# NNLightSwitcher_DDR3.net
KiCad netlist of a schematic drawn in Altium Designer
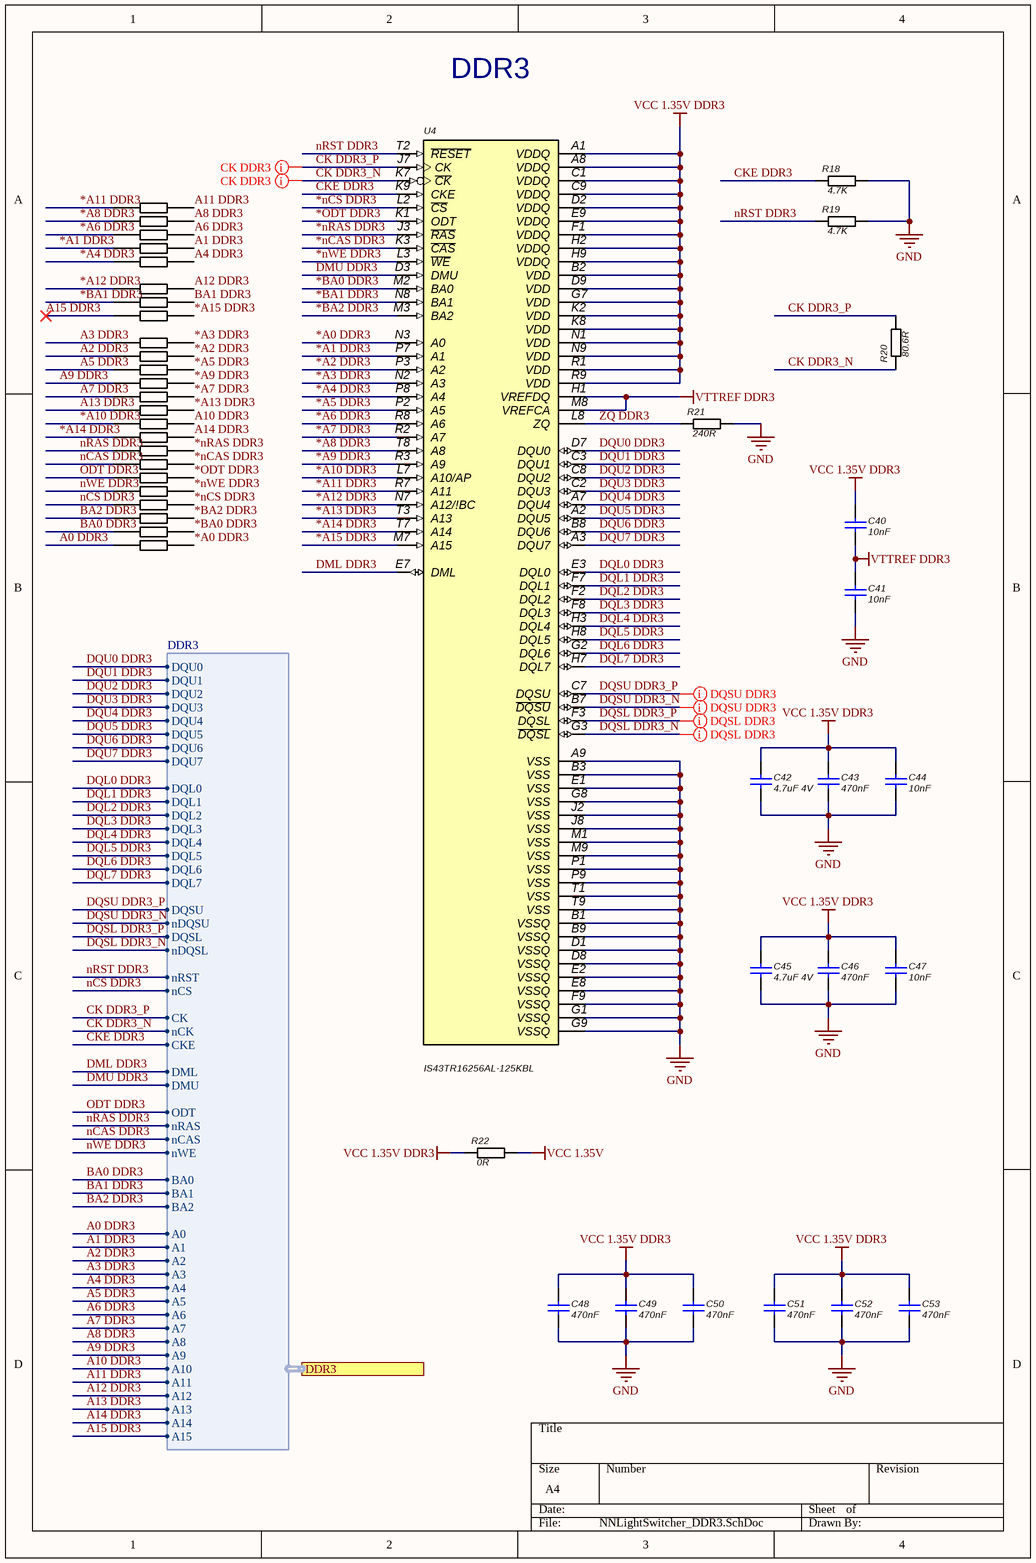
[diagram p0: NNLightSwitcher_DDR3.SchDoc]

(export (version "E")
  (design (tool "Eeschema 10.0.6"))
  (components
    (comp (ref "C40")
      (value "10nF")
      (footprint "0402")
      (libsource (lib "NNLightSwitcher") (part "Capacitor 10nF"))
    )
    (comp (ref "C41")
      (value "10nF")
      (footprint "0402")
      (libsource (lib "NNLightSwitcher") (part "Capacitor 10nF"))
    )
    (comp (ref "C42")
      (value "4.7uF 4V")
      (footprint "0402")
      (libsource (lib "NNLightSwitcher") (part "Capacitor 4.7uF 4V"))
    )
    (comp (ref "C43")
      (value "470nF")
      (footprint "0402")
      (libsource (lib "NNLightSwitcher") (part "Capacitor 470nF"))
    )
    (comp (ref "C44")
      (value "10nF")
      (footprint "0402")
      (libsource (lib "NNLightSwitcher") (part "Capacitor 10nF"))
    )
    (comp (ref "C45")
      (value "4.7uF 4V")
      (footprint "0402")
      (libsource (lib "NNLightSwitcher") (part "Capacitor 4.7uF 4V"))
    )
    (comp (ref "C46")
      (value "470nF")
      (footprint "0402")
      (libsource (lib "NNLightSwitcher") (part "Capacitor 470nF"))
    )
    (comp (ref "C47")
      (value "10nF")
      (footprint "0402")
      (libsource (lib "NNLightSwitcher") (part "Capacitor 10nF"))
    )
    (comp (ref "C48")
      (value "470nF")
      (footprint "0402")
      (libsource (lib "NNLightSwitcher") (part "Capacitor 470nF"))
    )
    (comp (ref "C49")
      (value "470nF")
      (footprint "0402")
      (libsource (lib "NNLightSwitcher") (part "Capacitor 470nF"))
    )
    (comp (ref "C50")
      (value "470nF")
      (footprint "0402")
      (libsource (lib "NNLightSwitcher") (part "Capacitor 470nF"))
    )
    (comp (ref "C51")
      (value "470nF")
      (footprint "0402")
      (libsource (lib "NNLightSwitcher") (part "Capacitor 470nF"))
    )
    (comp (ref "C52")
      (value "470nF")
      (footprint "0402")
      (libsource (lib "NNLightSwitcher") (part "Capacitor 470nF"))
    )
    (comp (ref "C53")
      (value "470nF")
      (footprint "0402")
      (libsource (lib "NNLightSwitcher") (part "Capacitor 470nF"))
    )
    (comp (ref "R18")
      (value "4.7K")
      (footprint "0402")
      (libsource (lib "NNLightSwitcher") (part "Resistor 4.7K"))
    )
    (comp (ref "R19")
      (value "4.7K")
      (footprint "0402")
      (libsource (lib "NNLightSwitcher") (part "Resistor 4.7K"))
    )
    (comp (ref "R20")
      (value "80.6R")
      (footprint "0402")
      (libsource (lib "NNLightSwitcher") (part "Resistor 80.6R"))
    )
    (comp (ref "R21")
      (value "240R")
      (footprint "0402")
      (libsource (lib "NNLightSwitcher") (part "Resistor 240R"))
    )
    (comp (ref "R22")
      (value "0R")
      (footprint "0402")
      (libsource (lib "NNLightSwitcher") (part "Resistor 0R"))
    )
    (comp (ref "RN1")
      (value "EXB-2HV431JV")
      (footprint "*RESCAXE50P380X160X55-16N")
      (description "Res Thick Film Array")
      (libsource (lib "NNLightSwitcher") (part "EXB-2HV431JV"))
    )
    (comp (ref "RN2")
      (value "EXB-2HV431JV")
      (footprint "*RESCAXE50P380X160X55-16N")
      (description "Res Thick Film Array")
      (libsource (lib "NNLightSwitcher") (part "EXB-2HV431JV"))
    )
    (comp (ref "RN3")
      (value "EXB-2HV431JV")
      (footprint "*RESCAXE50P380X160X55-16N")
      (description "Res Thick Film Array")
      (libsource (lib "NNLightSwitcher") (part "EXB-2HV431JV"))
    )
    (comp (ref "U4")
      (value "IS43TR16256AL-125KBL")
      (footprint "*BGA96C80P9X16_900X1300X120_IS43TR16256AL-125KBL(Primary)")
      (description "4G, 1.35V, DDR3L, 256Mx16, 1600MT/s @ 11-11-11, 96 ball BGA _9mm x13mm_ RoHS")
      (libsource (lib "NNLightSwitcher") (part "IS43TR16256AL-125KBL"))
    )
  )
  (nets
    (net (code "2") (name "/*A0 DDR3") (class "Default")
      (node (ref "RN3") (pin "9") (pinfunction "2_9") (pintype "passive"))
      (node (ref "U4") (pin "N3") (pinfunction "A0_N3") (pintype "input"))
    )
    (net (code "3") (name "/*A1 DDR3") (class "Default")
      (node (ref "RN1") (pin "4") (pinfunction "1_4") (pintype "passive"))
      (node (ref "U4") (pin "P7") (pinfunction "A1_P7") (pintype "input"))
    )
    (net (code "4") (name "/*A2 DDR3") (class "Default")
      (node (ref "RN2") (pin "15") (pinfunction "2_15") (pintype "passive"))
      (node (ref "U4") (pin "P3") (pinfunction "A2_P3") (pintype "input"))
    )
    (net (code "5") (name "/*A3 DDR3") (class "Default")
      (node (ref "RN2") (pin "16") (pinfunction "2_16") (pintype "passive"))
      (node (ref "U4") (pin "N2") (pinfunction "A3_N2") (pintype "input"))
    )
    (net (code "6") (name "/*A4 DDR3") (class "Default")
      (node (ref "RN1") (pin "5") (pinfunction "1_5") (pintype "passive"))
      (node (ref "U4") (pin "P8") (pinfunction "A4_P8") (pintype "input"))
    )
    (net (code "7") (name "/*A5 DDR3") (class "Default")
      (node (ref "RN2") (pin "14") (pinfunction "2_14") (pintype "passive"))
      (node (ref "U4") (pin "P2") (pinfunction "A5_P2") (pintype "input"))
    )
    (net (code "8") (name "/*A6 DDR3") (class "Default")
      (node (ref "RN1") (pin "3") (pinfunction "1_3") (pintype "passive"))
      (node (ref "U4") (pin "R8") (pinfunction "A6_R8") (pintype "input"))
    )
    (net (code "9") (name "/*A7 DDR3") (class "Default")
      (node (ref "RN2") (pin "12") (pinfunction "2_12") (pintype "passive"))
      (node (ref "U4") (pin "R2") (pinfunction "A7_R2") (pintype "input"))
    )
    (net (code "10") (name "/*A8 DDR3") (class "Default")
      (node (ref "RN1") (pin "2") (pinfunction "1_2") (pintype "passive"))
      (node (ref "U4") (pin "T8") (pinfunction "A8_T8") (pintype "input"))
    )
    (net (code "11") (name "/*A9 DDR3") (class "Default")
      (node (ref "RN2") (pin "13") (pinfunction "2_13") (pintype "passive"))
      (node (ref "U4") (pin "R3") (pinfunction "A9_R3") (pintype "input"))
    )
    (net (code "12") (name "/*A10 DDR3") (class "Default")
      (node (ref "RN2") (pin "7") (pinfunction "1_7") (pintype "passive"))
      (node (ref "U4") (pin "L7") (pinfunction "A10/AP_L7") (pintype "input"))
    )
    (net (code "13") (name "/*A11 DDR3") (class "Default")
      (node (ref "RN1") (pin "1") (pinfunction "1_1") (pintype "passive"))
      (node (ref "U4") (pin "R7") (pinfunction "A11_R7") (pintype "input"))
    )
    (net (code "14") (name "/*A12 DDR3") (class "Default")
      (node (ref "RN1") (pin "6") (pinfunction "1_6") (pintype "passive"))
      (node (ref "U4") (pin "N7") (pinfunction "A12/!BC_N7") (pintype "input"))
    )
    (net (code "15") (name "/*A13 DDR3") (class "Default")
      (node (ref "RN2") (pin "11") (pinfunction "2_11") (pintype "passive"))
      (node (ref "U4") (pin "T3") (pinfunction "A13_T3") (pintype "input"))
    )
    (net (code "16") (name "/*A14 DDR3") (class "Default")
      (node (ref "RN2") (pin "8") (pinfunction "1_8") (pintype "passive"))
      (node (ref "U4") (pin "T7") (pinfunction "A14_T7") (pintype "input"))
    )
    (net (code "17") (name "/*A15 DDR3") (class "Default")
      (node (ref "RN1") (pin "8") (pinfunction "1_8") (pintype "passive"))
      (node (ref "U4") (pin "M7") (pinfunction "A15_M7") (pintype "input"))
    )
    (net (code "18") (name "/*BA0 DDR3") (class "Default")
      (node (ref "RN3") (pin "10") (pinfunction "2_10") (pintype "passive"))
      (node (ref "U4") (pin "M2") (pinfunction "BA0_M2") (pintype "input"))
    )
    (net (code "19") (name "/*BA1 DDR3") (class "Default")
      (node (ref "RN1") (pin "7") (pinfunction "1_7") (pintype "passive"))
      (node (ref "U4") (pin "N8") (pinfunction "BA1_N8") (pintype "input"))
    )
    (net (code "20") (name "/*BA2 DDR3") (class "Default")
      (node (ref "RN3") (pin "11") (pinfunction "2_11") (pintype "passive"))
      (node (ref "U4") (pin "M3") (pinfunction "BA2_M3") (pintype "input"))
    )
    (net (code "21") (name "/*ODT DDR3") (class "Default")
      (node (ref "RN3") (pin "14") (pinfunction "2_14") (pintype "passive"))
      (node (ref "U4") (pin "K1") (pinfunction "ODT_K1") (pintype "input"))
    )
    (net (code "22") (name "/*nCAS DDR3") (class "Default")
      (node (ref "RN3") (pin "15") (pinfunction "2_15") (pintype "passive"))
      (node (ref "U4") (pin "K3") (pinfunction "~{CAS}_K3") (pintype "input"))
    )
    (net (code "23") (name "/*nCS DDR3") (class "Default")
      (node (ref "RN3") (pin "12") (pinfunction "2_12") (pintype "passive"))
      (node (ref "U4") (pin "L2") (pinfunction "~{CS}_L2") (pintype "input"))
    )
    (net (code "24") (name "/*nRAS DDR3") (class "Default")
      (node (ref "RN3") (pin "16") (pinfunction "2_16") (pintype "passive"))
      (node (ref "U4") (pin "J3") (pinfunction "~{RAS}_J3") (pintype "input"))
    )
    (net (code "25") (name "/*nWE DDR3") (class "Default")
      (node (ref "RN3") (pin "13") (pinfunction "2_13") (pintype "passive"))
      (node (ref "U4") (pin "L3") (pinfunction "~{WE}_L3") (pintype "input"))
    )
    (net (code "26") (name "/A0 DDR3") (class "Default")
      (node (ref "RN3") (pin "8") (pinfunction "1_8") (pintype "passive"))
    )
    (net (code "27") (name "/A1 DDR3") (class "Default")
      (node (ref "RN1") (pin "13") (pinfunction "2_13") (pintype "passive"))
    )
    (net (code "28") (name "/A2 DDR3") (class "Default")
      (node (ref "RN2") (pin "2") (pinfunction "1_2") (pintype "passive"))
    )
    (net (code "29") (name "/A3 DDR3") (class "Default")
      (node (ref "RN2") (pin "1") (pinfunction "1_1") (pintype "passive"))
    )
    (net (code "30") (name "/A4 DDR3") (class "Default")
      (node (ref "RN1") (pin "12") (pinfunction "2_12") (pintype "passive"))
    )
    (net (code "31") (name "/A5 DDR3") (class "Default")
      (node (ref "RN2") (pin "3") (pinfunction "1_3") (pintype "passive"))
    )
    (net (code "32") (name "/A6 DDR3") (class "Default")
      (node (ref "RN1") (pin "14") (pinfunction "2_14") (pintype "passive"))
    )
    (net (code "33") (name "/A7 DDR3") (class "Default")
      (node (ref "RN2") (pin "5") (pinfunction "1_5") (pintype "passive"))
    )
    (net (code "34") (name "/A8 DDR3") (class "Default")
      (node (ref "RN1") (pin "15") (pinfunction "2_15") (pintype "passive"))
    )
    (net (code "35") (name "/A9 DDR3") (class "Default")
      (node (ref "RN2") (pin "4") (pinfunction "1_4") (pintype "passive"))
    )
    (net (code "36") (name "/A10 DDR3") (class "Default")
      (node (ref "RN2") (pin "10") (pinfunction "2_10") (pintype "passive"))
    )
    (net (code "37") (name "/A11 DDR3") (class "Default")
      (node (ref "RN1") (pin "16") (pinfunction "2_16") (pintype "passive"))
    )
    (net (code "38") (name "/A12 DDR3") (class "Default")
      (node (ref "RN1") (pin "11") (pinfunction "2_11") (pintype "passive"))
    )
    (net (code "39") (name "/A13 DDR3") (class "Default")
      (node (ref "RN2") (pin "6") (pinfunction "1_6") (pintype "passive"))
    )
    (net (code "40") (name "/A14 DDR3") (class "Default")
      (node (ref "RN2") (pin "9") (pinfunction "2_9") (pintype "passive"))
    )
    (net (code "41") (name "/A15 DDR3") (class "Default")
      (node (ref "RN1") (pin "9") (pinfunction "2_9") (pintype "passive"))
    )
    (net (code "42") (name "/BA0 DDR3") (class "Default")
      (node (ref "RN3") (pin "7") (pinfunction "1_7") (pintype "passive"))
    )
    (net (code "43") (name "/BA1 DDR3") (class "Default")
      (node (ref "RN1") (pin "10") (pinfunction "2_10") (pintype "passive"))
    )
    (net (code "44") (name "/BA2 DDR3") (class "Default")
      (node (ref "RN3") (pin "6") (pinfunction "1_6") (pintype "passive"))
    )
    (net (code "45") (name "/CK DDR3_N") (class "Default")
      (node (ref "R20") (pin "1") (pinfunction "1_1") (pintype "passive"))
      (node (ref "U4") (pin "K7") (pinfunction "~{CK}_K7") (pintype "input"))
    )
    (net (code "46") (name "/CK DDR3_P") (class "Default")
      (node (ref "R20") (pin "2") (pinfunction "2_2") (pintype "passive"))
      (node (ref "U4") (pin "J7") (pinfunction "CK_J7") (pintype "input"))
    )
    (net (code "47") (name "/CKE DDR3") (class "Default")
      (node (ref "R18") (pin "1") (pinfunction "1_1") (pintype "passive"))
      (node (ref "U4") (pin "K9") (pinfunction "CKE_K9") (pintype "input"))
    )
    (net (code "48") (name "/DML DDR3") (class "Default")
      (node (ref "U4") (pin "E7") (pinfunction "DML_E7") (pintype "bidirectional"))
    )
    (net (code "49") (name "/DMU DDR3") (class "Default")
      (node (ref "U4") (pin "D3") (pinfunction "DMU_D3") (pintype "input"))
    )
    (net (code "50") (name "/DQL0 DDR3") (class "Default")
      (node (ref "U4") (pin "E3") (pinfunction "DQL0_E3") (pintype "bidirectional"))
    )
    (net (code "51") (name "/DQL1 DDR3") (class "Default")
      (node (ref "U4") (pin "F7") (pinfunction "DQL1_F7") (pintype "bidirectional"))
    )
    (net (code "52") (name "/DQL2 DDR3") (class "Default")
      (node (ref "U4") (pin "F2") (pinfunction "DQL2_F2") (pintype "bidirectional"))
    )
    (net (code "53") (name "/DQL3 DDR3") (class "Default")
      (node (ref "U4") (pin "F8") (pinfunction "DQL3_F8") (pintype "bidirectional"))
    )
    (net (code "54") (name "/DQL4 DDR3") (class "Default")
      (node (ref "U4") (pin "H3") (pinfunction "DQL4_H3") (pintype "bidirectional"))
    )
    (net (code "55") (name "/DQL5 DDR3") (class "Default")
      (node (ref "U4") (pin "H8") (pinfunction "DQL5_H8") (pintype "bidirectional"))
    )
    (net (code "56") (name "/DQL6 DDR3") (class "Default")
      (node (ref "U4") (pin "G2") (pinfunction "DQL6_G2") (pintype "bidirectional"))
    )
    (net (code "57") (name "/DQL7 DDR3") (class "Default")
      (node (ref "U4") (pin "H7") (pinfunction "DQL7_H7") (pintype "bidirectional"))
    )
    (net (code "58") (name "/DQSL DDR3_N") (class "Default")
      (node (ref "U4") (pin "G3") (pinfunction "~{DQSL}_G3") (pintype "bidirectional"))
    )
    (net (code "59") (name "/DQSL DDR3_P") (class "Default")
      (node (ref "U4") (pin "F3") (pinfunction "DQSL_F3") (pintype "bidirectional"))
    )
    (net (code "60") (name "/DQSU DDR3_N") (class "Default")
      (node (ref "U4") (pin "B7") (pinfunction "~{DQSU}_B7") (pintype "bidirectional"))
    )
    (net (code "61") (name "/DQSU DDR3_P") (class "Default")
      (node (ref "U4") (pin "C7") (pinfunction "DQSU_C7") (pintype "bidirectional"))
    )
    (net (code "62") (name "/DQU0 DDR3") (class "Default")
      (node (ref "U4") (pin "D7") (pinfunction "DQU0_D7") (pintype "bidirectional"))
    )
    (net (code "63") (name "/DQU1 DDR3") (class "Default")
      (node (ref "U4") (pin "C3") (pinfunction "DQU1_C3") (pintype "bidirectional"))
    )
    (net (code "64") (name "/DQU2 DDR3") (class "Default")
      (node (ref "U4") (pin "C8") (pinfunction "DQU2_C8") (pintype "bidirectional"))
    )
    (net (code "65") (name "/DQU3 DDR3") (class "Default")
      (node (ref "U4") (pin "C2") (pinfunction "DQU3_C2") (pintype "bidirectional"))
    )
    (net (code "66") (name "/DQU4 DDR3") (class "Default")
      (node (ref "U4") (pin "A7") (pinfunction "DQU4_A7") (pintype "bidirectional"))
    )
    (net (code "67") (name "/DQU5 DDR3") (class "Default")
      (node (ref "U4") (pin "A2") (pinfunction "DQU5_A2") (pintype "bidirectional"))
    )
    (net (code "68") (name "/DQU6 DDR3") (class "Default")
      (node (ref "U4") (pin "B8") (pinfunction "DQU6_B8") (pintype "bidirectional"))
    )
    (net (code "69") (name "/DQU7 DDR3") (class "Default")
      (node (ref "U4") (pin "A3") (pinfunction "DQU7_A3") (pintype "bidirectional"))
    )
    (net (code "70") (name "/ODT DDR3") (class "Default")
      (node (ref "RN3") (pin "3") (pinfunction "1_3") (pintype "passive"))
    )
    (net (code "71") (name "/ZQ DDR3") (class "Default")
      (node (ref "R21") (pin "1") (pinfunction "1_1") (pintype "passive"))
      (node (ref "U4") (pin "L8") (pinfunction "ZQ_L8") (pintype "power_in"))
    )
    (net (code "72") (name "/nCAS DDR3") (class "Default")
      (node (ref "RN3") (pin "2") (pinfunction "1_2") (pintype "passive"))
    )
    (net (code "73") (name "/nCS DDR3") (class "Default")
      (node (ref "RN3") (pin "5") (pinfunction "1_5") (pintype "passive"))
    )
    (net (code "74") (name "/nRAS DDR3") (class "Default")
      (node (ref "RN3") (pin "1") (pinfunction "1_1") (pintype "passive"))
    )
    (net (code "75") (name "/nRST DDR3") (class "Default")
      (node (ref "R19") (pin "1") (pinfunction "1_1") (pintype "passive"))
      (node (ref "U4") (pin "T2") (pinfunction "~{RESET}_T2") (pintype "input"))
    )
    (net (code "76") (name "/nWE DDR3") (class "Default")
      (node (ref "RN3") (pin "4") (pinfunction "1_4") (pintype "passive"))
    )
    (net (code "78") (name "GND") (class "Default")
      (node (ref "C41") (pin "2") (pinfunction "2_2") (pintype "passive"))
      (node (ref "C42") (pin "2") (pinfunction "2_2") (pintype "passive"))
      (node (ref "C43") (pin "2") (pinfunction "2_2") (pintype "passive"))
      (node (ref "C44") (pin "2") (pinfunction "2_2") (pintype "passive"))
      (node (ref "C45") (pin "2") (pinfunction "2_2") (pintype "passive"))
      (node (ref "C46") (pin "2") (pinfunction "2_2") (pintype "passive"))
      (node (ref "C47") (pin "2") (pinfunction "2_2") (pintype "passive"))
      (node (ref "C48") (pin "2") (pinfunction "2_2") (pintype "passive"))
      (node (ref "C49") (pin "2") (pinfunction "2_2") (pintype "passive"))
      (node (ref "C50") (pin "2") (pinfunction "2_2") (pintype "passive"))
      (node (ref "C51") (pin "2") (pinfunction "2_2") (pintype "passive"))
      (node (ref "C52") (pin "2") (pinfunction "2_2") (pintype "passive"))
      (node (ref "C53") (pin "2") (pinfunction "2_2") (pintype "passive"))
      (node (ref "R18") (pin "2") (pinfunction "2_2") (pintype "passive"))
      (node (ref "R19") (pin "2") (pinfunction "2_2") (pintype "passive"))
      (node (ref "R21") (pin "2") (pinfunction "2_2") (pintype "passive"))
      (node (ref "U4") (pin "A9") (pinfunction "VSS_A9") (pintype "power_in"))
      (node (ref "U4") (pin "B1") (pinfunction "VSSQ_B1") (pintype "power_in"))
      (node (ref "U4") (pin "B3") (pinfunction "VSS_B3") (pintype "power_in"))
      (node (ref "U4") (pin "B9") (pinfunction "VSSQ_B9") (pintype "power_in"))
      (node (ref "U4") (pin "D1") (pinfunction "VSSQ_D1") (pintype "power_in"))
      (node (ref "U4") (pin "D8") (pinfunction "VSSQ_D8") (pintype "power_in"))
      (node (ref "U4") (pin "E1") (pinfunction "VSS_E1") (pintype "power_in"))
      (node (ref "U4") (pin "E2") (pinfunction "VSSQ_E2") (pintype "power_in"))
      (node (ref "U4") (pin "E8") (pinfunction "VSSQ_E8") (pintype "power_in"))
      (node (ref "U4") (pin "F9") (pinfunction "VSSQ_F9") (pintype "power_in"))
      (node (ref "U4") (pin "G1") (pinfunction "VSSQ_G1") (pintype "power_in"))
      (node (ref "U4") (pin "G8") (pinfunction "VSS_G8") (pintype "power_in"))
      (node (ref "U4") (pin "G9") (pinfunction "VSSQ_G9") (pintype "power_in"))
      (node (ref "U4") (pin "J2") (pinfunction "VSS_J2") (pintype "power_in"))
      (node (ref "U4") (pin "J8") (pinfunction "VSS_J8") (pintype "power_in"))
      (node (ref "U4") (pin "M1") (pinfunction "VSS_M1") (pintype "power_in"))
      (node (ref "U4") (pin "M9") (pinfunction "VSS_M9") (pintype "power_in"))
      (node (ref "U4") (pin "P1") (pinfunction "VSS_P1") (pintype "power_in"))
      (node (ref "U4") (pin "P9") (pinfunction "VSS_P9") (pintype "power_in"))
      (node (ref "U4") (pin "T1") (pinfunction "VSS_T1") (pintype "power_in"))
      (node (ref "U4") (pin "T9") (pinfunction "VSS_T9") (pintype "power_in"))
    )
    (net (code "79") (name "VCC 1.35V") (class "Default")
      (node (ref "R22") (pin "2") (pinfunction "2_2") (pintype "passive"))
    )
    (net (code "80") (name "VCC 1.35V DDR3") (class "Default")
      (node (ref "C40") (pin "1") (pinfunction "1_1") (pintype "passive"))
      (node (ref "C42") (pin "1") (pinfunction "1_1") (pintype "passive"))
      (node (ref "C43") (pin "1") (pinfunction "1_1") (pintype "passive"))
      (node (ref "C44") (pin "1") (pinfunction "1_1") (pintype "passive"))
      (node (ref "C45") (pin "1") (pinfunction "1_1") (pintype "passive"))
      (node (ref "C46") (pin "1") (pinfunction "1_1") (pintype "passive"))
      (node (ref "C47") (pin "1") (pinfunction "1_1") (pintype "passive"))
      (node (ref "C48") (pin "1") (pinfunction "1_1") (pintype "passive"))
      (node (ref "C49") (pin "1") (pinfunction "1_1") (pintype "passive"))
      (node (ref "C50") (pin "1") (pinfunction "1_1") (pintype "passive"))
      (node (ref "C51") (pin "1") (pinfunction "1_1") (pintype "passive"))
      (node (ref "C52") (pin "1") (pinfunction "1_1") (pintype "passive"))
      (node (ref "C53") (pin "1") (pinfunction "1_1") (pintype "passive"))
      (node (ref "R22") (pin "1") (pinfunction "1_1") (pintype "passive"))
      (node (ref "U4") (pin "A1") (pinfunction "VDDQ_A1") (pintype "power_in"))
      (node (ref "U4") (pin "A8") (pinfunction "VDDQ_A8") (pintype "power_in"))
      (node (ref "U4") (pin "B2") (pinfunction "VDD_B2") (pintype "power_in"))
      (node (ref "U4") (pin "C1") (pinfunction "VDDQ_C1") (pintype "power_in"))
      (node (ref "U4") (pin "C9") (pinfunction "VDDQ_C9") (pintype "power_in"))
      (node (ref "U4") (pin "D2") (pinfunction "VDDQ_D2") (pintype "power_in"))
      (node (ref "U4") (pin "D9") (pinfunction "VDD_D9") (pintype "power_in"))
      (node (ref "U4") (pin "E9") (pinfunction "VDDQ_E9") (pintype "power_in"))
      (node (ref "U4") (pin "F1") (pinfunction "VDDQ_F1") (pintype "power_in"))
      (node (ref "U4") (pin "G7") (pinfunction "VDD_G7") (pintype "power_in"))
      (node (ref "U4") (pin "H2") (pinfunction "VDDQ_H2") (pintype "power_in"))
      (node (ref "U4") (pin "H9") (pinfunction "VDDQ_H9") (pintype "power_in"))
      (node (ref "U4") (pin "K2") (pinfunction "VDD_K2") (pintype "power_in"))
      (node (ref "U4") (pin "K8") (pinfunction "VDD_K8") (pintype "power_in"))
      (node (ref "U4") (pin "N1") (pinfunction "VDD_N1") (pintype "power_in"))
      (node (ref "U4") (pin "N9") (pinfunction "VDD_N9") (pintype "power_in"))
      (node (ref "U4") (pin "R1") (pinfunction "VDD_R1") (pintype "power_in"))
      (node (ref "U4") (pin "R9") (pinfunction "VDD_R9") (pintype "power_in"))
    )
    (net (code "81") (name "VTTREF DDR3") (class "Default")
      (node (ref "C40") (pin "2") (pinfunction "2_2") (pintype "passive"))
      (node (ref "C41") (pin "1") (pinfunction "1_1") (pintype "passive"))
      (node (ref "U4") (pin "H1") (pinfunction "VREFDQ_H1") (pintype "power_in"))
      (node (ref "U4") (pin "M8") (pinfunction "VREFCA_M8") (pintype "power_in"))
    )
  )
)
